# USB_BAT.net
KiCad netlist of a schematic drawn in Altium Designer
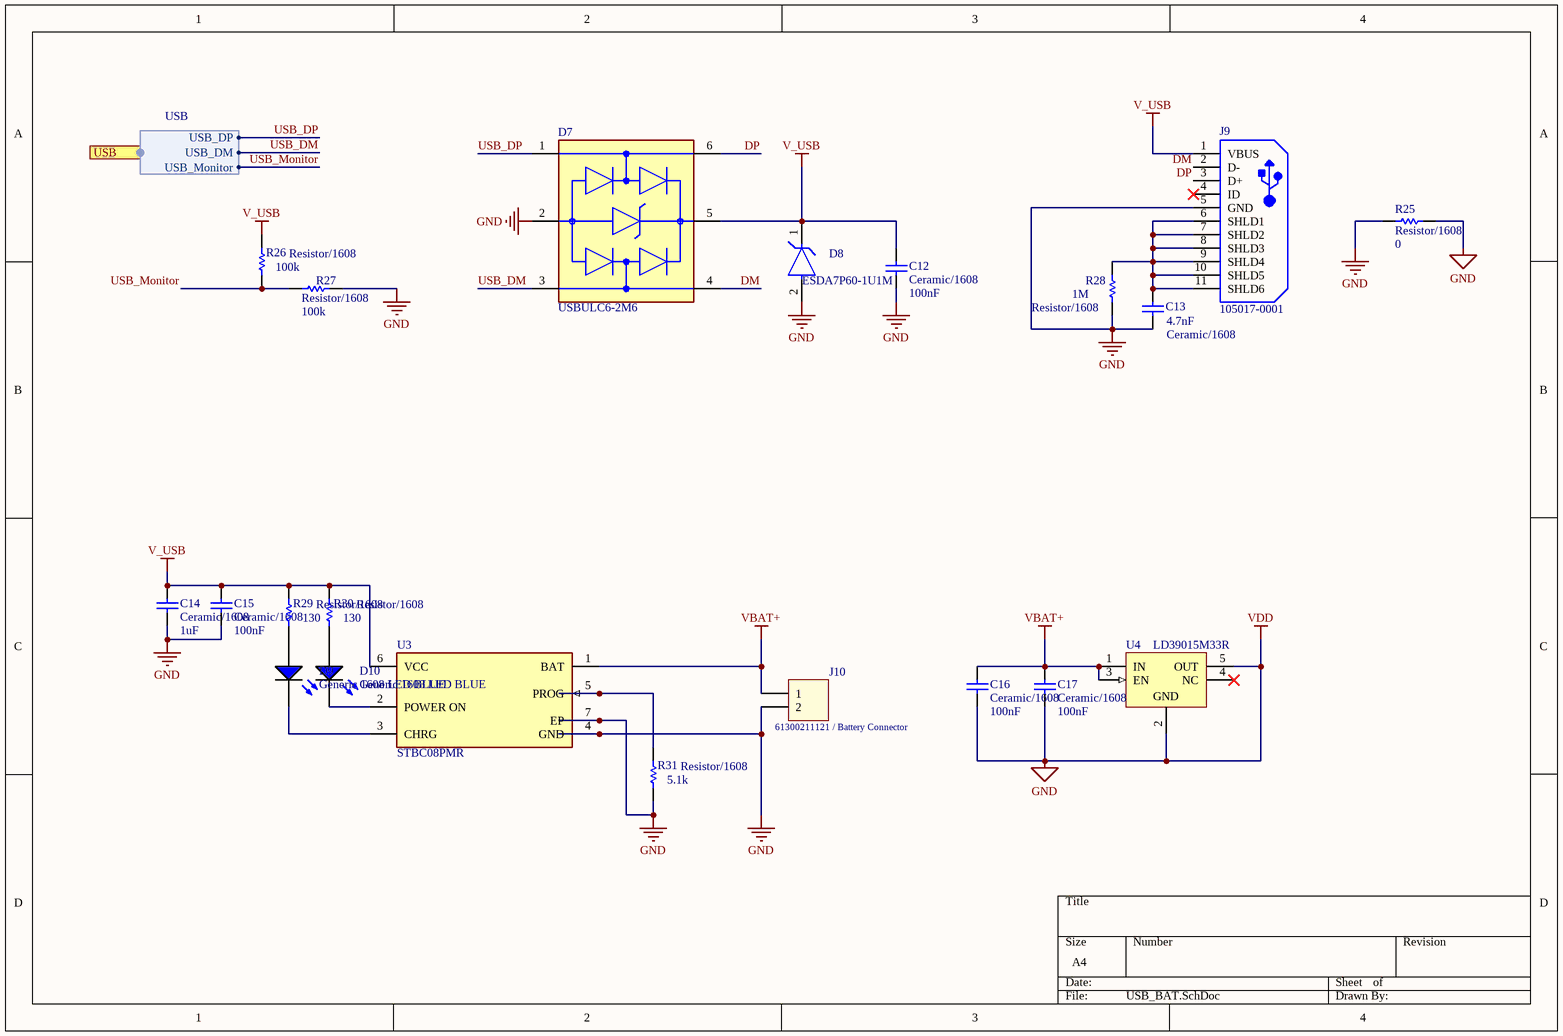
[diagram p0: USB_BAT.SchDoc]

(export (version "E")
  (design (tool "Eeschema 10.0.6"))
  (components
    (comp (ref "C12")
      (value "Ceramic/1608")
      (footprint "Generic 1608 Ceramic")
      (description "Generic 1608 Ceramic Capacitor")
      (fields (field (name "ALTIUM_VALUE") "100nF"))
      (libsource (lib "C6H6`s Vault") (part "Generic 1608"))
    )
    (comp (ref "C13")
      (value "Ceramic/1608")
      (footprint "Generic 1608 Ceramic")
      (description "Generic 1608 Ceramic Capacitor / 50V")
      (fields (field (name "ALTIUM_VALUE") "4.7nF"))
      (libsource (lib "C6H6`s Vault") (part "Generic 1608"))
    )
    (comp (ref "C14")
      (value "Ceramic/1608")
      (footprint "Generic 1608 Ceramic")
      (description "Generic 1608 Ceramic Capacitor")
      (fields (field (name "ALTIUM_VALUE") "1uF"))
      (libsource (lib "C6H6`s Vault") (part "Generic 1608"))
    )
    (comp (ref "C15")
      (value "Ceramic/1608")
      (footprint "Generic 1608 Ceramic")
      (description "Generic 1608 Ceramic Capacitor")
      (fields (field (name "ALTIUM_VALUE") "100nF"))
      (libsource (lib "C6H6`s Vault") (part "Generic 1608"))
    )
    (comp (ref "C16")
      (value "Ceramic/1608")
      (footprint "Generic 1608 Ceramic")
      (description "Generic 1608 Ceramic Capacitor")
      (fields (field (name "ALTIUM_VALUE") "100nF"))
      (libsource (lib "C6H6`s Vault") (part "Generic 1608"))
    )
    (comp (ref "C17")
      (value "Ceramic/1608")
      (footprint "Generic 1608 Ceramic")
      (description "Generic 1608 Ceramic Capacitor")
      (fields (field (name "ALTIUM_VALUE") "100nF"))
      (libsource (lib "C6H6`s Vault") (part "Generic 1608"))
    )
    (comp (ref "D7")
      (value "USBULC6-2M6")
      (footprint "FP-QFN_1_45x1_00_6L-MFG")
      (description "TVS DIODE 5V 17V 6UQFN")
      (fields
        (field (name "MANUFACTURER") "STMicroelectronics")
        (field (name "OCTOPART") "https://octopart.com/usbulc6-2m6-stmicroelectronics-7979994")
      )
      (libsource (lib "Altium Content Vault") (part "2a068c5d1761ebb85bd110cdb84ff95"))
    )
    (comp (ref "D8")
      (value "ESDA7P60-1U1M")
      (footprint "FP-1610-MFG")
      (description "TVS DIODE 5V 11.6V 1610")
      (fields
        (field (name "MANUFACTURER") "STMicroelectronics")
        (field (name "OCTOPART") "https://octopart.com/esda7p60-1u1m-stmicroelectronics-52112702")
      )
      (libsource (lib "Altium Content Vault") (part "f813f71cba58e380607f5dd3caf9714"))
    )
    (comp (ref "D9")
      (value "Generic 1608 LED BLUE")
      (footprint "Generic 1608 LED BLUE-Footprint-1")
      (description "Generic 1608 LED <BLUE>")
      (libsource (lib "C6H6`s Vault") (part "1608/BLUE"))
    )
    (comp (ref "D10")
      (value "Generic 1608 LED BLUE")
      (footprint "Generic 1608 LED BLUE-Footprint-1")
      (description "Generic 1608 LED <BLUE>")
      (libsource (lib "C6H6`s Vault") (part "1608/BLUE"))
    )
    (comp (ref "J9")
      (value "105017-0001")
      (footprint "USB-MICRO-B_V")
      (fields (field (name "MANUFACTURER") "Molex"))
      (libsource (lib "Altium Content Vault") (part "USB-5-6SHLD"))
    )
    (comp (ref "J10")
      (value "61300211121 / Battery Connector")
      (footprint "61300211121")
      (description "Pin Header WR-PHD, pitch 2.54 mm, THT, Vertical, single row, 2 pin")
      (fields (field (name "PART NUMBER") "61300211121") (field (name "PUBLISHER") "Wurth Elektronik"))
      (libsource (lib "C6H6`s Vault") (part "61300211121"))
    )
    (comp (ref "R25")
      (value "Resistor/1608")
      (footprint "Resistor 1608-Footprint")
      (description "Generic 1608 Resistor")
      (fields (field (name "ALTIUM_VALUE") "0"))
      (libsource (lib "C6H6`s Vault") (part "Resistor 1608"))
    )
    (comp (ref "R26")
      (value "Resistor/1608")
      (footprint "Resistor 1608-Footprint")
      (description "Generic 1608 Resistor")
      (fields (field (name "ALTIUM_VALUE") "100k"))
      (libsource (lib "C6H6`s Vault") (part "Resistor 1608"))
    )
    (comp (ref "R27")
      (value "Resistor/1608")
      (footprint "Resistor 1608-Footprint")
      (description "Generic 1608 Resistor")
      (fields (field (name "ALTIUM_VALUE") "100k"))
      (libsource (lib "C6H6`s Vault") (part "Resistor 1608"))
    )
    (comp (ref "R28")
      (value "Resistor/1608")
      (footprint "Resistor 1608-Footprint")
      (description "Generic 1608 Resistor")
      (fields (field (name "ALTIUM_VALUE") "1M"))
      (libsource (lib "C6H6`s Vault") (part "Resistor 1608"))
    )
    (comp (ref "R29")
      (value "Resistor/1608")
      (footprint "Resistor 1608-Footprint")
      (description "Generic 1608 Resistor")
      (fields (field (name "ALTIUM_VALUE") "130"))
      (libsource (lib "C6H6`s Vault") (part "Resistor 1608"))
    )
    (comp (ref "R30")
      (value "Resistor/1608")
      (footprint "Resistor 1608-Footprint")
      (description "Generic 1608 Resistor")
      (fields (field (name "ALTIUM_VALUE") "130"))
      (libsource (lib "C6H6`s Vault") (part "Resistor 1608"))
    )
    (comp (ref "R31")
      (value "Resistor/1608")
      (footprint "Resistor 1608-Footprint")
      (description "Generic 1608 Resistor")
      (fields (field (name "ALTIUM_VALUE") "5.1k"))
      (libsource (lib "C6H6`s Vault") (part "Resistor 1608"))
    )
    (comp (ref "U3")
      (value "STBC08PMR")
      (footprint "FP-DFN6-7946637-IPC_A")
      (description "IC BATT CHRGR LI-ION 800MA DFN6")
      (libsource (lib "Altium Content Vault") (part "0eb1821a720559127d84c19dad45f09"))
    )
    (comp (ref "U4")
      (value "LD39015M33R")
      (footprint "SOT23-5L_M")
      (description "150 mA Low Quiescent Current Low Noise Voltage Regulator, 3.3V, 5-Pin SOT-23, Tape and Reel")
      (libsource (lib "Altium Content Vault") (part "PM-REG-LD39015M-SOT5"))
    )
  )
  (nets
    (net (code "2") (name "/DM") (class "Default")
      (node (ref "D7") (pin "4") (pinfunction "I/O2_4") (pintype "passive"))
      (node (ref "J9") (pin "2") (pinfunction "D-_2") (pintype "passive"))
    )
    (net (code "3") (name "/DP") (class "Default")
      (node (ref "D7") (pin "6") (pinfunction "I/O1_6") (pintype "passive"))
      (node (ref "J9") (pin "3") (pinfunction "D+_3") (pintype "passive"))
    )
    (net (code "4") (name "/USB_DM") (class "Default")
      (node (ref "D7") (pin "3") (pinfunction "I/O2_3") (pintype "passive"))
    )
    (net (code "5") (name "/USB_DP") (class "Default")
      (node (ref "D7") (pin "1") (pinfunction "I/O1_1") (pintype "passive"))
    )
    (net (code "6") (name "/USB_Monitor") (class "Default")
      (node (ref "R26") (pin "1") (pinfunction "1_1") (pintype "passive"))
      (node (ref "R27") (pin "2") (pinfunction "2_2") (pintype "passive"))
    )
    (net (code "8") (name "GND") (class "Default")
      (node (ref "C12") (pin "1") (pinfunction "1_1") (pintype "passive"))
      (node (ref "C13") (pin "1") (pinfunction "1_1") (pintype "passive"))
      (node (ref "C14") (pin "1") (pinfunction "1_1") (pintype "passive"))
      (node (ref "C15") (pin "1") (pinfunction "1_1") (pintype "passive"))
      (node (ref "C16") (pin "1") (pinfunction "1_1") (pintype "passive"))
      (node (ref "C17") (pin "1") (pinfunction "1_1") (pintype "passive"))
      (node (ref "D7") (pin "2") (pinfunction "2_2") (pintype "passive"))
      (node (ref "D8") (pin "2") (pinfunction "A_2") (pintype "passive"))
      (node (ref "J10") (pin "2") (pinfunction "2_2") (pintype "passive"))
      (node (ref "J9") (pin "5") (pinfunction "GND_5") (pintype "passive"))
      (node (ref "R25") (pin "1") (pinfunction "1_1") (pintype "passive"))
      (node (ref "R25") (pin "2") (pinfunction "2_2") (pintype "passive"))
      (node (ref "R27") (pin "1") (pinfunction "1_1") (pintype "passive"))
      (node (ref "R28") (pin "1") (pinfunction "1_1") (pintype "passive"))
      (node (ref "R31") (pin "1") (pinfunction "1_1") (pintype "passive"))
      (node (ref "U3") (pin "4") (pinfunction "GND_4") (pintype "power_in"))
      (node (ref "U3") (pin "7") (pinfunction "EP_7") (pintype "power_in"))
      (node (ref "U4") (pin "2") (pinfunction "GND_2") (pintype "power_in"))
      (node (ref "U4") (pin "5") (pinfunction "OUT_5") (pintype "power_in"))
    )
    (net (code "9") (name "Net-(D9-A)") (class "Default")
      (node (ref "D9") (pin "1") (pinfunction "A_1") (pintype "passive"))
      (node (ref "R29") (pin "1") (pinfunction "1_1") (pintype "passive"))
    )
    (net (code "10") (name "Net-(D9-K)") (class "Default")
      (node (ref "D9") (pin "2") (pinfunction "K_2") (pintype "passive"))
      (node (ref "U3") (pin "3") (pinfunction "CHRG_3") (pintype "open_collector"))
    )
    (net (code "11") (name "Net-(D10-A)") (class "Default")
      (node (ref "D10") (pin "1") (pinfunction "A_1") (pintype "passive"))
      (node (ref "R30") (pin "1") (pinfunction "1_1") (pintype "passive"))
    )
    (net (code "12") (name "Net-(D10-K)") (class "Default")
      (node (ref "D10") (pin "2") (pinfunction "K_2") (pintype "passive"))
      (node (ref "U3") (pin "2") (pinfunction "POWER_ON_2") (pintype "open_collector"))
    )
    (net (code "13") (name "Net-(J9-SHLD1)") (class "Default")
      (node (ref "C13") (pin "2") (pinfunction "2_2") (pintype "passive"))
      (node (ref "J9") (pin "10") (pinfunction "SHLD5_10") (pintype "passive"))
      (node (ref "J9") (pin "11") (pinfunction "SHLD6_11") (pintype "passive"))
      (node (ref "J9") (pin "6") (pinfunction "SHLD1_6") (pintype "passive"))
      (node (ref "J9") (pin "7") (pinfunction "SHLD2_7") (pintype "passive"))
      (node (ref "J9") (pin "8") (pinfunction "SHLD3_8") (pintype "passive"))
      (node (ref "J9") (pin "9") (pinfunction "SHLD4_9") (pintype "passive"))
      (node (ref "R28") (pin "2") (pinfunction "2_2") (pintype "passive"))
    )
    (net (code "14") (name "Net-(U3-PROG)") (class "Default")
      (node (ref "R31") (pin "2") (pinfunction "2_2") (pintype "passive"))
      (node (ref "U3") (pin "5") (pinfunction "PROG_5") (pintype "input"))
    )
    (net (code "15") (name "VBAT+") (class "Default")
      (node (ref "C16") (pin "2") (pinfunction "2_2") (pintype "passive"))
      (node (ref "C17") (pin "2") (pinfunction "2_2") (pintype "passive"))
      (node (ref "J10") (pin "1") (pinfunction "1_1") (pintype "passive"))
      (node (ref "U3") (pin "1") (pinfunction "BAT_1") (pintype "power_in"))
      (node (ref "U4") (pin "1") (pinfunction "IN_1") (pintype "power_in"))
      (node (ref "U4") (pin "3") (pinfunction "EN_3") (pintype "input"))
    )
    (net (code "16") (name "V_USB") (class "Default")
      (node (ref "C12") (pin "2") (pinfunction "2_2") (pintype "passive"))
      (node (ref "C14") (pin "2") (pinfunction "2_2") (pintype "passive"))
      (node (ref "C15") (pin "2") (pinfunction "2_2") (pintype "passive"))
      (node (ref "D7") (pin "5") (pinfunction "5_5") (pintype "passive"))
      (node (ref "D8") (pin "1") (pinfunction "C_1") (pintype "passive"))
      (node (ref "J9") (pin "1") (pinfunction "VBUS_1") (pintype "passive"))
      (node (ref "R26") (pin "2") (pinfunction "2_2") (pintype "passive"))
      (node (ref "R29") (pin "2") (pinfunction "2_2") (pintype "passive"))
      (node (ref "R30") (pin "2") (pinfunction "2_2") (pintype "passive"))
      (node (ref "U3") (pin "6") (pinfunction "VCC_6") (pintype "power_in"))
    )
    (net (code "17") (name "unconnected-(J9-ID-Pad4)") (class "Default")
      (node (ref "J9") (pin "4") (pinfunction "ID_4") (pintype "passive+no_connect"))
    )
    (net (code "18") (name "unconnected-(U4-NC-Pad4)") (class "Default")
      (node (ref "U4") (pin "4") (pinfunction "NC_4") (pintype "passive+no_connect"))
    )
  )
)
